# altimeter.net
KiCad netlist of a schematic drawn in EAGLE
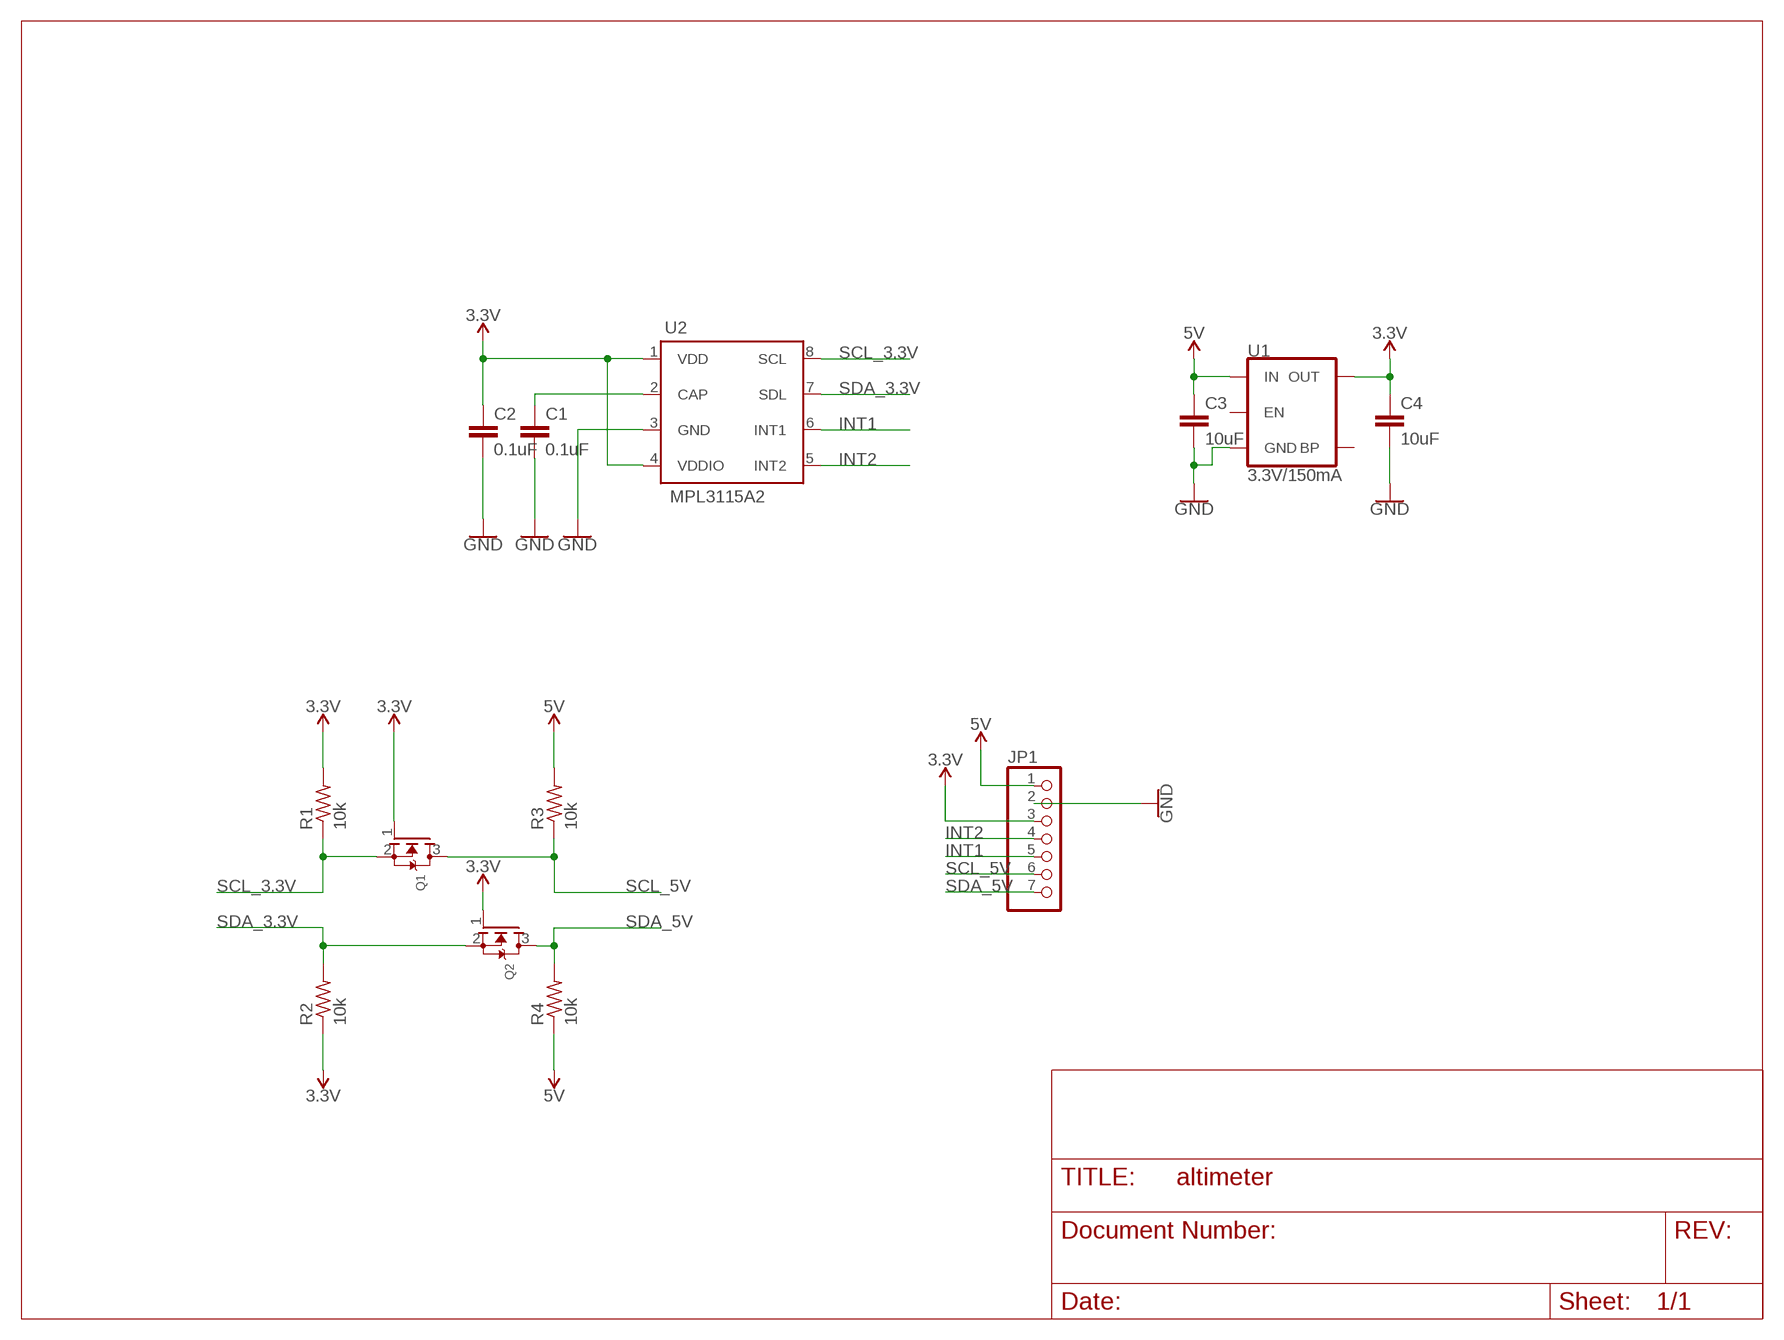
[diagram p0: schematic, sheet 1]

(export (version "E")
  (design (tool "Eeschema 10.0.6"))
  (components
    (comp (ref "C1")
      (value "0.1uF")
      (footprint "eagle-import:C0805")
      (libsource (lib "eagle-import") (part "C-EUC0805"))
    )
    (comp (ref "C2")
      (value "0.1uF")
      (footprint "eagle-import:C0805")
      (libsource (lib "eagle-import") (part "C-EUC0805"))
    )
    (comp (ref "C3")
      (value "10uF")
      (footprint "eagle-import:C0805")
      (libsource (lib "eagle-import") (part "C-EUC0805"))
    )
    (comp (ref "C4")
      (value "10uF")
      (footprint "eagle-import:C0805")
      (libsource (lib "eagle-import") (part "C-EUC0805"))
    )
    (comp (ref "JP1")
      (value "PINHD-1X7")
      (footprint "eagle-import:1X07")
      (libsource (lib "eagle-import") (part "PINHD-1X7"))
    )
    (comp (ref "Q1")
      (value "MOSFET-NWAVE")
      (footprint "eagle-import:SOT23-W")
      (libsource (lib "eagle-import") (part "MOSFET-NWAVE"))
    )
    (comp (ref "Q2")
      (value "MOSFET-NWAVE")
      (footprint "eagle-import:SOT23-W")
      (libsource (lib "eagle-import") (part "MOSFET-NWAVE"))
    )
    (comp (ref "R1")
      (value "10k")
      (footprint "eagle-import:R0805")
      (libsource (lib "eagle-import") (part "R-US_R0805"))
    )
    (comp (ref "R2")
      (value "10k")
      (footprint "eagle-import:R0805")
      (libsource (lib "eagle-import") (part "R-US_R0805"))
    )
    (comp (ref "R3")
      (value "10k")
      (footprint "eagle-import:R0805")
      (libsource (lib "eagle-import") (part "R-US_R0805"))
    )
    (comp (ref "R4")
      (value "10k")
      (footprint "eagle-import:R0805")
      (libsource (lib "eagle-import") (part "R-US_R0805"))
    )
    (comp (ref "U1")
      (value "3.3V/150mA")
      (footprint "eagle-import:SOT23-5")
      (libsource (lib "eagle-import") (part "V_REG_MIC52053.3V"))
    )
    (comp (ref "U2")
      (value "MPL3115A2")
      (footprint "eagle-import:LGA8")
      (libsource (lib "eagle-import") (part "MPL3115A2"))
    )
  )
  (nets
    (net (code "1") (name "/INT1") (class "Default")
      (node (ref "JP1") (pin "5") (pinfunction "5_5") (pintype "passive"))
      (node (ref "U2") (pin "6") (pinfunction "INT1_6") (pintype "bidirectional"))
    )
    (net (code "2") (name "/INT2") (class "Default")
      (node (ref "JP1") (pin "4") (pinfunction "4_4") (pintype "passive"))
      (node (ref "U2") (pin "5") (pinfunction "INT2_5") (pintype "bidirectional"))
    )
    (net (code "3") (name "/SCL_3.3V") (class "Default")
      (node (ref "Q1") (pin "2") (pinfunction "S_2") (pintype "bidirectional"))
      (node (ref "R1") (pin "1") (pinfunction "1_1") (pintype "passive"))
      (node (ref "U2") (pin "8") (pinfunction "SCL_8") (pintype "bidirectional"))
    )
    (net (code "4") (name "/SCL_5V") (class "Default")
      (node (ref "JP1") (pin "6") (pinfunction "6_6") (pintype "passive"))
      (node (ref "Q1") (pin "3") (pinfunction "D_3") (pintype "bidirectional"))
      (node (ref "R3") (pin "1") (pinfunction "1_1") (pintype "passive"))
    )
    (net (code "5") (name "/SDA_3.3V") (class "Default")
      (node (ref "Q2") (pin "2") (pinfunction "S_2") (pintype "bidirectional"))
      (node (ref "R2") (pin "2") (pinfunction "2_2") (pintype "passive"))
      (node (ref "U2") (pin "7") (pinfunction "SDL_7") (pintype "bidirectional"))
    )
    (net (code "6") (name "/SDA_5V") (class "Default")
      (node (ref "JP1") (pin "7") (pinfunction "7_7") (pintype "passive"))
      (node (ref "Q2") (pin "3") (pinfunction "D_3") (pintype "bidirectional"))
      (node (ref "R4") (pin "2") (pinfunction "2_2") (pintype "passive"))
    )
    (net (code "7") (name "3.3V") (class "Default")
      (node (ref "C2") (pin "1") (pinfunction "1_1") (pintype "passive"))
      (node (ref "C4") (pin "1") (pinfunction "1_1") (pintype "passive"))
      (node (ref "JP1") (pin "3") (pinfunction "3_3") (pintype "passive"))
      (node (ref "Q1") (pin "1") (pinfunction "G_1") (pintype "bidirectional"))
      (node (ref "Q2") (pin "1") (pinfunction "G_1") (pintype "bidirectional"))
      (node (ref "R1") (pin "2") (pinfunction "2_2") (pintype "passive"))
      (node (ref "R2") (pin "1") (pinfunction "1_1") (pintype "passive"))
      (node (ref "U1") (pin "5") (pinfunction "OUT_5") (pintype "passive"))
      (node (ref "U2") (pin "1") (pinfunction "VDD_1") (pintype "power_in"))
      (node (ref "U2") (pin "4") (pinfunction "VDDIO_4") (pintype "power_in"))
    )
    (net (code "8") (name "5V") (class "Default")
      (node (ref "C3") (pin "1") (pinfunction "1_1") (pintype "passive"))
      (node (ref "JP1") (pin "1") (pinfunction "1_1") (pintype "passive"))
      (node (ref "R3") (pin "2") (pinfunction "2_2") (pintype "passive"))
      (node (ref "R4") (pin "1") (pinfunction "1_1") (pintype "passive"))
      (node (ref "U1") (pin "1") (pinfunction "IN_1") (pintype "input"))
    )
    (net (code "9") (name "GND") (class "Default")
      (node (ref "C1") (pin "2") (pinfunction "2_2") (pintype "passive"))
      (node (ref "C2") (pin "2") (pinfunction "2_2") (pintype "passive"))
      (node (ref "C3") (pin "2") (pinfunction "2_2") (pintype "passive"))
      (node (ref "C4") (pin "2") (pinfunction "2_2") (pintype "passive"))
      (node (ref "JP1") (pin "2") (pinfunction "2_2") (pintype "passive"))
      (node (ref "U1") (pin "2") (pinfunction "GND_2") (pintype "input"))
      (node (ref "U2") (pin "3") (pinfunction "GND_3") (pintype "power_in"))
    )
    (net (code "10") (name "Net-(U2-CAP)") (class "Default")
      (node (ref "C1") (pin "1") (pinfunction "1_1") (pintype "passive"))
      (node (ref "U2") (pin "2") (pinfunction "CAP_2") (pintype "bidirectional"))
    )
    (net (code "11") (name "unconnected-(U1-BP-Pad4)") (class "Default")
      (node (ref "U1") (pin "4") (pinfunction "BP_4") (pintype "input"))
    )
    (net (code "12") (name "unconnected-(U1-EN-Pad3)") (class "Default")
      (node (ref "U1") (pin "3") (pinfunction "EN_3") (pintype "input"))
    )
  )
)
